# IR_distance_interrupter.net
KiCad netlist of a schematic drawn in EAGLE
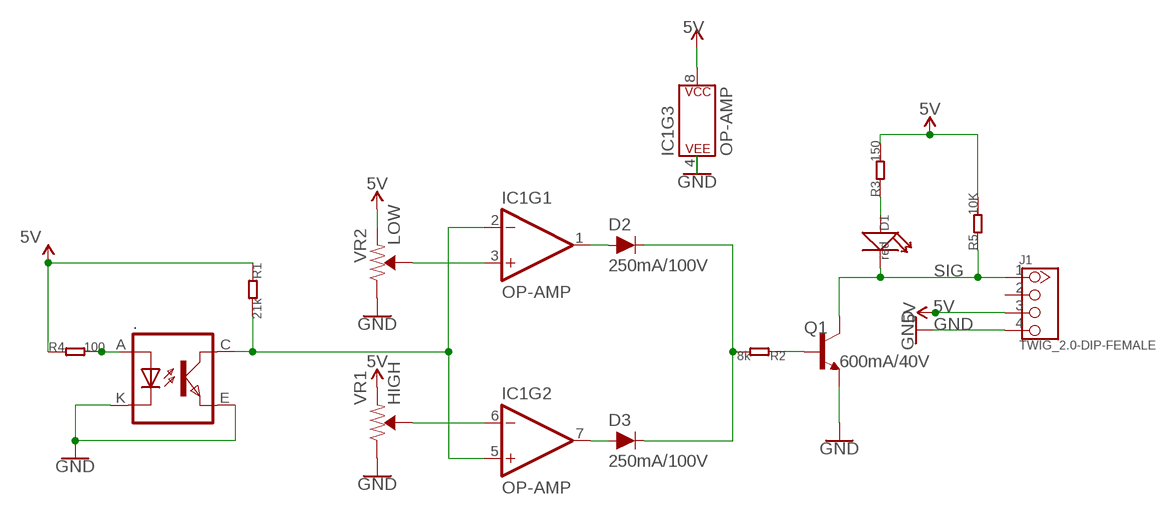
[diagram p0: schematic, sheet 1]

(export (version "E")
  (design (tool "Eeschema 10.0.6"))
  (components
    (comp (ref ".")
      (value "TCRT5000")
      (footprint "eagle-import:TCRT5000")
      (libsource (lib "eagle-import") (part "TCRT5000"))
    )
    (comp (ref "D1")
      (value "red")
      (footprint "eagle-import:LED0603")
      (libsource (lib "eagle-import") (part "007-LED3540"))
    )
    (comp (ref "D2")
      (value "250mA/100V")
      (footprint "eagle-import:SOD-323")
      (libsource (lib "eagle-import") (part "DIODE-BAS16J"))
    )
    (comp (ref "D3")
      (value "250mA/100V")
      (footprint "eagle-import:SOD-323")
      (libsource (lib "eagle-import") (part "DIODE-BAS16J"))
    )
    (comp (ref "IC1")
      (value "OP-AMP")
      (footprint "eagle-import:SO08")
      (libsource (lib "eagle-import") (part "OPAMP-DUALU"))
    )
    (comp (ref "J1")
      (value "TWIG_2.0-DIP-FEMALE")
      (footprint "eagle-import:2.0_1X4")
      (libsource (lib "eagle-import") (part "TWIG_2.0-DIP-FEMALE"))
    )
    (comp (ref "Q1")
      (value "600mA/40V")
      (footprint "eagle-import:SOT23-3")
      (libsource (lib "eagle-import") (part "TRANS_NPN-MMBT2222AL"))
    )
    (comp (ref "R1")
      (value "21k")
      (footprint "eagle-import:0603_S")
      (libsource (lib "eagle-import") (part "005-R0603_S"))
    )
    (comp (ref "R2")
      (value "8k")
      (footprint "eagle-import:0603_S")
      (libsource (lib "eagle-import") (part "005-R0603_S"))
    )
    (comp (ref "R3")
      (value "150")
      (footprint "eagle-import:0603_S")
      (libsource (lib "eagle-import") (part "005-R0603_S"))
    )
    (comp (ref "R4")
      (value "100")
      (footprint "eagle-import:0603_S")
      (libsource (lib "eagle-import") (part "005-R0603_S"))
    )
    (comp (ref "R5")
      (value "10K")
      (footprint "eagle-import:0603_S")
      (libsource (lib "eagle-import") (part "005-R0603_S"))
    )
    (comp (ref "VR1")
      (value "HIGH")
      (footprint "eagle-import:TRIMPOT-SMD-5MM")
      (libsource (lib "eagle-import") (part "TRIMPOT-SMD-5MM-CLOSED-1/4W-20%"))
    )
    (comp (ref "VR2")
      (value "LOW")
      (footprint "eagle-import:TRIMPOT-SMD-5MM")
      (libsource (lib "eagle-import") (part "TRIMPOT-SMD-5MM-CLOSED-1/4W-20%"))
    )
  )
  (nets
    (net (code "1") (name "/SIG") (class "Default")
      (node (ref "D1") (pin "2") (pinfunction "-_2") (pintype "passive"))
      (node (ref "J1") (pin "1") (pinfunction "1_1") (pintype "bidirectional"))
      (node (ref "Q1") (pin "3") (pinfunction "C_3") (pintype "passive"))
      (node (ref "R5") (pin "1") (pinfunction "1_1") (pintype "passive"))
    )
    (net (code "2") (name "5V") (class "Default")
      (node (ref "IC1") (pin "8") (pinfunction "P$V+_8") (pintype "bidirectional"))
      (node (ref "J1") (pin "3") (pinfunction "3_3") (pintype "bidirectional"))
      (node (ref "R1") (pin "1") (pinfunction "1_1") (pintype "passive"))
      (node (ref "R3") (pin "2") (pinfunction "2_2") (pintype "passive"))
      (node (ref "R4") (pin "1") (pinfunction "1_1") (pintype "passive"))
      (node (ref "R5") (pin "2") (pinfunction "2_2") (pintype "passive"))
      (node (ref "VR1") (pin "A") (pinfunction "CCW_A") (pintype "passive"))
      (node (ref "VR2") (pin "A") (pinfunction "CCW_A") (pintype "passive"))
    )
    (net (code "3") (name "GND") (class "Default")
      (node (ref ".") (pin "E") (pinfunction "EMITTER_E") (pintype "passive"))
      (node (ref ".") (pin "K") (pinfunction "CATHODE_K") (pintype "passive"))
      (node (ref "IC1") (pin "4") (pinfunction "P$V-_4") (pintype "bidirectional"))
      (node (ref "J1") (pin "4") (pinfunction "4_4") (pintype "bidirectional"))
      (node (ref "Q1") (pin "2") (pinfunction "E_2") (pintype "passive"))
      (node (ref "VR1") (pin "C") (pinfunction "CW_C") (pintype "passive"))
      (node (ref "VR2") (pin "C") (pinfunction "CW_C") (pintype "passive"))
    )
    (net (code "4") (name "Net-(.-ANODE)") (class "Default")
      (node (ref ".") (pin "A") (pinfunction "ANODE_A") (pintype "passive"))
      (node (ref "R4") (pin "2") (pinfunction "2_2") (pintype "passive"))
    )
    (net (code "5") (name "Net-(.-COLLECTOR)") (class "Default")
      (node (ref ".") (pin "C") (pinfunction "COLLECTOR_C") (pintype "passive"))
      (node (ref "IC1") (pin "2") (pinfunction "-IN_2") (pintype "input"))
      (node (ref "IC1") (pin "5") (pinfunction "+IN_5") (pintype "input"))
      (node (ref "R1") (pin "2") (pinfunction "2_2") (pintype "passive"))
    )
    (net (code "6") (name "Net-(D1-+)") (class "Default")
      (node (ref "D1") (pin "1") (pinfunction "+_1") (pintype "passive"))
      (node (ref "R3") (pin "1") (pinfunction "1_1") (pintype "passive"))
    )
    (net (code "7") (name "Net-(D2-PadC)") (class "Default")
      (node (ref "D2") (pin "C") (pinfunction "C_C") (pintype "passive"))
      (node (ref "D3") (pin "C") (pinfunction "C_C") (pintype "passive"))
      (node (ref "R2") (pin "2") (pinfunction "2_2") (pintype "passive"))
    )
    (net (code "8") (name "Net-(IC1A-+IN)") (class "Default")
      (node (ref "IC1") (pin "3") (pinfunction "+IN_3") (pintype "input"))
      (node (ref "VR2") (pin "B") (pinfunction "WIPER_B") (pintype "passive"))
    )
    (net (code "9") (name "Net-(IC1A-OUT)") (class "Default")
      (node (ref "D2") (pin "A") (pinfunction "A_A") (pintype "passive"))
      (node (ref "IC1") (pin "1") (pinfunction "OUT_1") (pintype "output"))
    )
    (net (code "10") (name "Net-(IC1B--IN)") (class "Default")
      (node (ref "IC1") (pin "6") (pinfunction "-IN_6") (pintype "input"))
      (node (ref "VR1") (pin "B") (pinfunction "WIPER_B") (pintype "passive"))
    )
    (net (code "11") (name "Net-(IC1B-OUT)") (class "Default")
      (node (ref "D3") (pin "A") (pinfunction "A_A") (pintype "passive"))
      (node (ref "IC1") (pin "7") (pinfunction "OUT_7") (pintype "output"))
    )
    (net (code "12") (name "Net-(Q1-B)") (class "Default")
      (node (ref "Q1") (pin "1") (pinfunction "B_1") (pintype "passive"))
      (node (ref "R2") (pin "1") (pinfunction "1_1") (pintype "passive"))
    )
    (net (code "13") (name "unconnected-(J1-Pad2)") (class "Default")
      (node (ref "J1") (pin "2") (pinfunction "2_2") (pintype "bidirectional"))
    )
  )
)
